# ChassisPowerDistribution_B_1_0_RW.net
KiCad netlist of a schematic drawn in Altium Designer
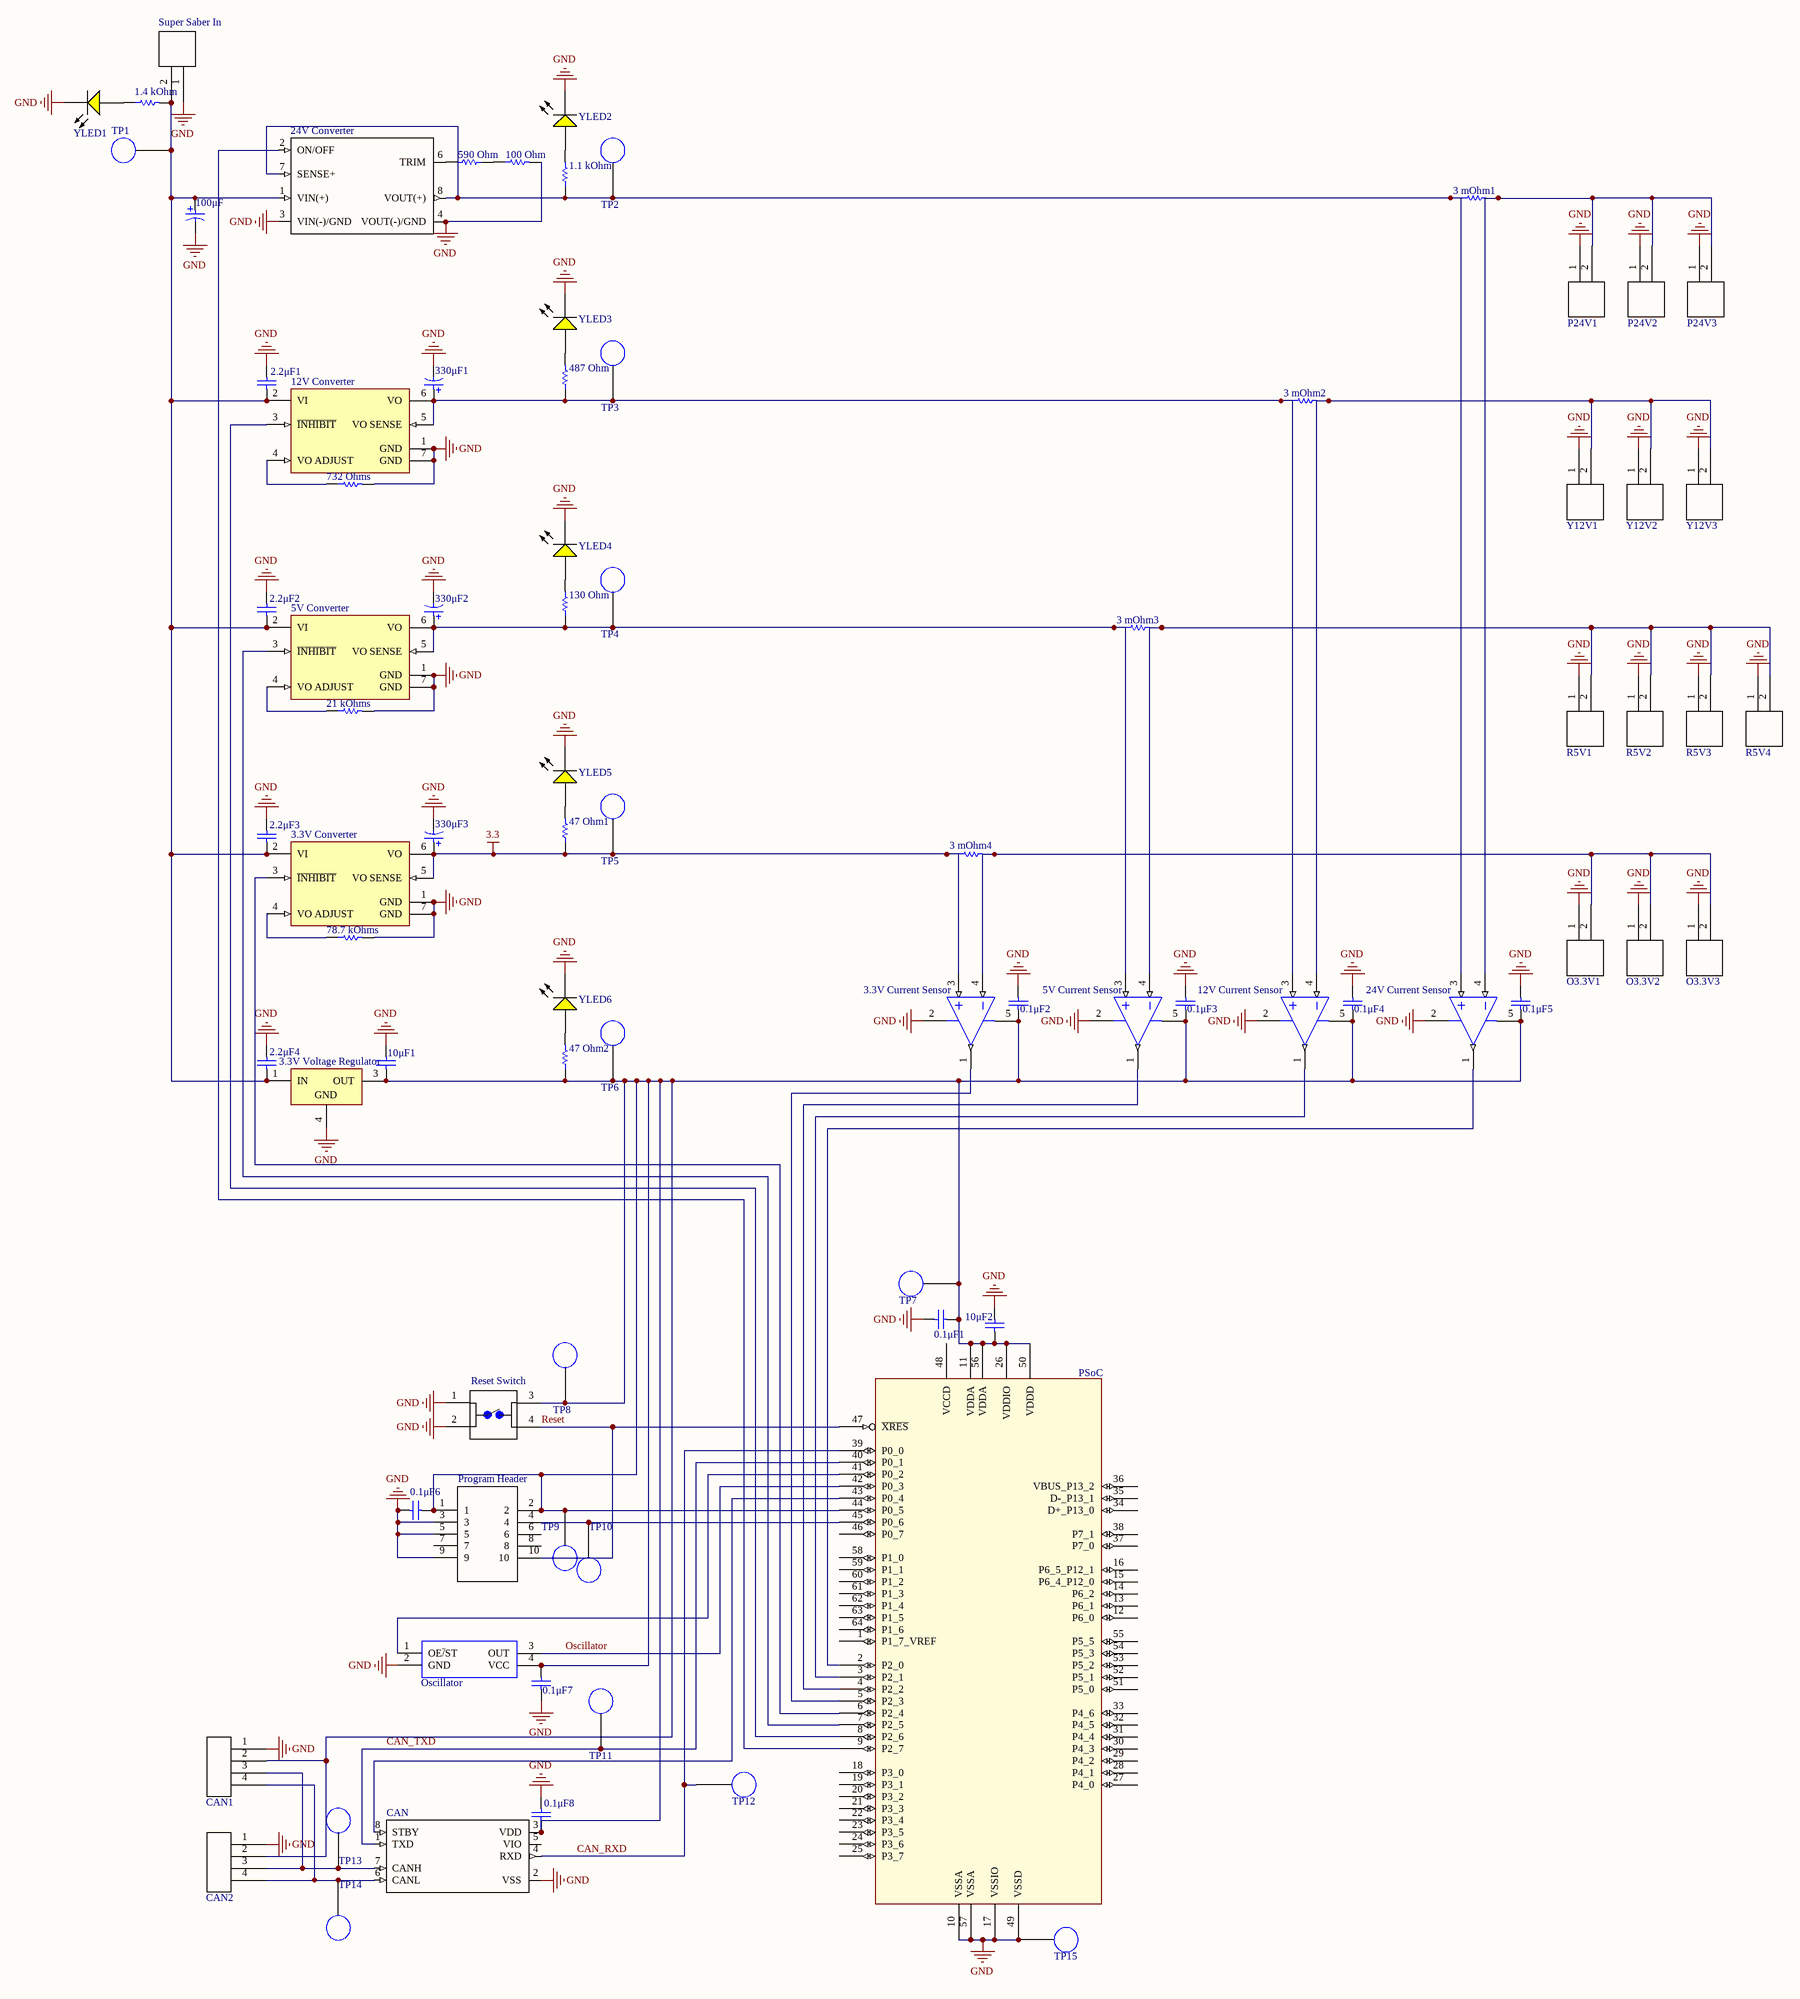
[diagram p0: ChassisPowerDistribution_B_1.0_RW.SchDoc]

(export (version "E")
  (design (tool "Eeschema 10.0.6"))
  (components
    (comp (ref "0.1μF1")
      (value "C0805C104Z5VACTU")
      (footprint "CAPC2013X145X50LL20T25")
      (fields (field (name "MANUFACTURER") "Kemet"))
      (libsource (lib "Altium Content Vault") (part "CAP"))
    )
    (comp (ref "0.1μF2")
      (value "C0805C104Z5VACTU")
      (footprint "CAPC2013X145X50LL20T25")
      (fields (field (name "MANUFACTURER") "Kemet"))
      (libsource (lib "Altium Content Vault") (part "CAP"))
    )
    (comp (ref "0.1μF3")
      (value "C0805C104Z5VACTU")
      (footprint "CAPC2013X145X50LL20T25")
      (fields (field (name "MANUFACTURER") "Kemet"))
      (libsource (lib "Altium Content Vault") (part "CAP"))
    )
    (comp (ref "0.1μF4")
      (value "C0805C104Z5VACTU")
      (footprint "CAPC2013X145X50LL20T25")
      (fields (field (name "MANUFACTURER") "Kemet"))
      (libsource (lib "Altium Content Vault") (part "CAP"))
    )
    (comp (ref "0.1μF5")
      (value "C0805C104Z5VACTU")
      (footprint "CAPC2013X145X50LL20T25")
      (fields (field (name "MANUFACTURER") "Kemet"))
      (libsource (lib "Altium Content Vault") (part "CAP"))
    )
    (comp (ref "0.1μF6")
      (value "C0805C104Z5VACTU")
      (footprint "CAPC2013X145X50LL20T25")
      (fields (field (name "MANUFACTURER") "Kemet"))
      (libsource (lib "Altium Content Vault") (part "CAP"))
    )
    (comp (ref "0.1μF7")
      (value "C0805C104Z5VACTU")
      (footprint "CAPC2013X145X50LL20T25")
      (fields (field (name "MANUFACTURER") "Kemet"))
      (libsource (lib "Altium Content Vault") (part "CAP"))
    )
    (comp (ref "0.1μF8")
      (value "C0805C104Z5VACTU")
      (footprint "CAPC2013X145X50LL20T25")
      (fields (field (name "MANUFACTURER") "Kemet"))
      (libsource (lib "Altium Content Vault") (part "CAP"))
    )
    (comp (ref "1.1 kOhm")
      (value "ERJ-6GEYJ112V")
      (footprint "RESC2013X70X40ML20T20")
      (fields (field (name "MANUFACTURER") "Panasonic"))
      (libsource (lib "Altium Content Vault") (part "RES"))
    )
    (comp (ref "1.4 kOhm")
      (value "RC0805FR-071K4L")
      (footprint "RESC2013X60X35ML10T20")
      (fields (field (name "MANUFACTURER") "Yageo"))
      (libsource (lib "Altium Content Vault") (part "RES"))
    )
    (comp (ref "2.2μF1")
      (value "C2012X7R1H225K125AC")
      (footprint "CAPC2013X145X20LL20")
      (description "Chip Capacitor, 2.2 uF, +/- 10%, 50 V, -55 to 125 degC, 0805 (2012 Metric), RoHS, Tape and Reel")
      (fields (field (name "MANUFACTURER") "TDK") (field (name "TOLERANCE") "±10%"))
      (libsource (lib "Altium Content Vault") (part "CAP-NP-2"))
    )
    (comp (ref "2.2μF2")
      (value "C2012X7R1H225K125AC")
      (footprint "CAPC2013X145X20LL20")
      (description "Chip Capacitor, 2.2 uF, +/- 10%, 50 V, -55 to 125 degC, 0805 (2012 Metric), RoHS, Tape and Reel")
      (fields (field (name "MANUFACTURER") "TDK") (field (name "TOLERANCE") "±10%"))
      (libsource (lib "Altium Content Vault") (part "CAP-NP-2"))
    )
    (comp (ref "2.2μF3")
      (value "C2012X7R1H225K125AC")
      (footprint "CAPC2013X145X20LL20")
      (description "Chip Capacitor, 2.2 uF, +/- 10%, 50 V, -55 to 125 degC, 0805 (2012 Metric), RoHS, Tape and Reel")
      (fields (field (name "MANUFACTURER") "TDK") (field (name "TOLERANCE") "±10%"))
      (libsource (lib "Altium Content Vault") (part "CAP-NP-2"))
    )
    (comp (ref "2.2μF4")
      (value "C2012X7R1H225K125AC")
      (footprint "CAPC2013X145X20LL20")
      (description "Chip Capacitor, 2.2 uF, +/- 10%, 50 V, -55 to 125 degC, 0805 (2012 Metric), RoHS, Tape and Reel")
      (fields (field (name "MANUFACTURER") "TDK") (field (name "TOLERANCE") "±10%"))
      (libsource (lib "Altium Content Vault") (part "CAP-NP-2"))
    )
    (comp (ref "3 mOhm1")
      (value "OAR5R003JLF")
      (footprint "OAR5R003JLF:OAR5R003JLF")
      (description "Resistor")
      (libsource (lib "Miscellaneous Devices") (part "Res1"))
    )
    (comp (ref "3 mOhm2")
      (value "OAR5R003JLF")
      (footprint "OAR5R003JLF:OAR5R003JLF")
      (description "Resistor")
      (libsource (lib "Miscellaneous Devices") (part "Res1"))
    )
    (comp (ref "3 mOhm3")
      (value "OAR5R003JLF")
      (footprint "OAR5R003JLF:OAR5R003JLF")
      (description "Resistor")
      (libsource (lib "Miscellaneous Devices") (part "Res1"))
    )
    (comp (ref "3 mOhm4")
      (value "OAR5R003JLF")
      (footprint "OAR5R003JLF:OAR5R003JLF")
      (description "Resistor")
      (libsource (lib "Miscellaneous Devices") (part "Res1"))
    )
    (comp (ref "3.3V Converter")
      (value "PTN78020WAH")
      (footprint "EUK0007A")
      (fields (field (name "MANUFACTURER") "Texas Instruments"))
      (libsource (lib "Altium Content Vault") (part "TI-PTN780X0WEUX7_HEUX7"))
    )
    (comp (ref "3.3V Current Sensor")
      (value "INA194AIDBVR")
      (footprint "DBV0005A_M")
      (fields (field (name "MANUFACTURER") "Texas Instruments"))
      (libsource (lib "Altium Content Vault") (part "TI-INA1XXDBV5"))
    )
    (comp (ref "3.3V Voltage Regulator")
      (value "LP2950CDTX-3.3")
      (footprint "TD03B_M")
      (description "Series of Adjustable Micropower Voltage Regulators, 3-pin TO-252")
      (fields (field (name "MANUFACTURER") "National Semiconductor"))
      (libsource (lib "Altium Content Vault") (part "PM-REG-LM78M05-SOT3"))
    )
    (comp (ref "5V Converter")
      (value "PTN78020WAH")
      (footprint "EUK0007A")
      (fields (field (name "MANUFACTURER") "Texas Instruments"))
      (libsource (lib "Altium Content Vault") (part "TI-PTN780X0WEUX7_HEUX7"))
    )
    (comp (ref "5V Current Sensor")
      (value "INA194AIDBVR")
      (footprint "DBV0005A_M")
      (fields (field (name "MANUFACTURER") "Texas Instruments"))
      (libsource (lib "Altium Content Vault") (part "TI-INA1XXDBV5"))
    )
    (comp (ref "10μF1")
      (value "TPSR106K006R1000")
      (footprint "CAPC2113X140X50ML20T30")
      (fields (field (name "MANUFACTURER") "AVX Interconnect / Elco"))
      (libsource (lib "Altium Content Vault") (part "CAP"))
    )
    (comp (ref "10μF2")
      (value "TPSR106K006R1000")
      (footprint "CAPC2113X140X50ML20T30")
      (fields (field (name "MANUFACTURER") "AVX Interconnect / Elco"))
      (libsource (lib "Altium Content Vault") (part "CAP"))
    )
    (comp (ref "12V Converter")
      (value "PTN78020WAH")
      (footprint "EUK0007A")
      (fields (field (name "MANUFACTURER") "Texas Instruments"))
      (libsource (lib "Altium Content Vault") (part "TI-PTN780X0WEUX7_HEUX7"))
    )
    (comp (ref "12V Current Sensor")
      (value "INA194AIDBVR")
      (footprint "DBV0005A_M")
      (fields (field (name "MANUFACTURER") "Texas Instruments"))
      (libsource (lib "Altium Content Vault") (part "TI-INA1XXDBV5"))
    )
    (comp (ref "21 kOhms")
      (value "ERJ-6ENF2102V")
      (footprint "RESC2013X70X40ML20T20")
      (fields (field (name "MANUFACTURER") "Panasonic"))
      (libsource (lib "Altium Content Vault") (part "RES"))
    )
    (comp (ref "24V Converter")
      (value "I6A4W010A033V-001-R")
      (footprint "*TDK-LAMBDA_I6A4W020A033V-001-R")
      (description "Dc-Dc, Pcb Mount, Sixteenth Brick, Input 24vdc, Output 3.3-40v 20a, 250w, Neg Logic")
      (fields (field (name "DIGI-KEY_PART_NUMBER") "285-2670-ND") (field (name "MF") "TDK-Lambda Americas"))
      (libsource (lib "*") (part "I6A4W020A033V-001-R"))
    )
    (comp (ref "24V Current Sensor")
      (value "INA194AIDBVR")
      (footprint "DBV0005A_M")
      (fields (field (name "MANUFACTURER") "Texas Instruments"))
      (libsource (lib "Altium Content Vault") (part "TI-INA1XXDBV5"))
    )
    (comp (ref "47 Ohm1")
      (value "RR1220Q-470-D")
      (footprint "RESC2013X50X40LL20T20")
      (fields (field (name "MANUFACTURER") "Susumu"))
      (libsource (lib "Altium Content Vault") (part "RES"))
    )
    (comp (ref "47 Ohm2")
      (value "RR1220Q-470-D")
      (footprint "RESC2013X50X40LL20T20")
      (fields (field (name "MANUFACTURER") "Susumu"))
      (libsource (lib "Altium Content Vault") (part "RES"))
    )
    (comp (ref "78.7 kOhms")
      (value "ERJ-6ENF7872V")
      (footprint "RESC2013X70X40LL20T20")
      (fields (field (name "MANUFACTURER") "Panasonic"))
      (libsource (lib "Altium Content Vault") (part "RES"))
    )
    (comp (ref "100 Ohm")
      (value "ERJ-6ENF1000V")
      (footprint "RESC2013X70X40LL20T20")
      (description "Chip Resistor, 100 Ohm, +/- 1%, 0.125 W, -55 to 155 degC, 0805 (2012 Metric), RoHS, Tape and Reel")
      (fields (field (name "MANUFACTURER") "Panasonic"))
      (libsource (lib "Altium Content Vault") (part "RES-2"))
    )
    (comp (ref "100μF")
      (value "EEU-FC1V101")
      (footprint "CAPPRD350W60D800H2000:*CAPPRD350W60D800H2000")
      (fields (field (name "MANUFACTURER") "Panasonic"))
      (libsource (lib "CAPPRD350W60D800H2000") (part "PNSC-CAP-P-2"))
    )
    (comp (ref "130 Ohm")
      (value "RC0805JR-07130RL")
      (footprint "RESC2013X60X35ML10T20")
      (fields (field (name "MANUFACTURER") "Yageo"))
      (libsource (lib "Altium Content Vault") (part "RES"))
    )
    (comp (ref "330μF1")
      (value "EEU-FC1V331B")
      (footprint "CAPPRD350W60D800H2000:*CAPPRD350W60D800H2000")
      (fields (field (name "MANUFACTURER") "Panasonic"))
      (libsource (lib "CAPPRD350W60D800H2000") (part "PNSC-CAP-P-2"))
    )
    (comp (ref "330μF2")
      (value "EEU-FC1V331B")
      (footprint "CAPPRD350W60D800H2000:*CAPPRD350W60D800H2000")
      (fields (field (name "MANUFACTURER") "Panasonic"))
      (libsource (lib "CAPPRD350W60D800H2000") (part "PNSC-CAP-P-2"))
    )
    (comp (ref "330μF3")
      (value "EEU-FC1V331B")
      (footprint "CAPPRD350W60D800H2000:*CAPPRD350W60D800H2000")
      (fields (field (name "MANUFACTURER") "Panasonic"))
      (libsource (lib "CAPPRD350W60D800H2000") (part "PNSC-CAP-P-2"))
    )
    (comp (ref "487 Ohm")
      (value "RC0805FR-07487RL")
      (footprint "RESC2013X60X35NL10T20")
      (fields (field (name "MANUFACTURER") "Yageo"))
      (libsource (lib "Altium Content Vault") (part "RES"))
    )
    (comp (ref "590 Ohm")
      (value "ERJ-6ENF5900V")
      (footprint "RESC2013X70X40LL20T20")
      (fields (field (name "MANUFACTURER") "Panasonic"))
      (libsource (lib "Altium Content Vault") (part "RES"))
    )
    (comp (ref "732 Ohms")
      (value "ERJ-6ENF7320V")
      (footprint "RESC2013X70X40LL20T20")
      (fields (field (name "MANUFACTURER") "Panasonic"))
      (libsource (lib "Altium Content Vault") (part "RES"))
    )
    (comp (ref "CAN")
      (value "MCP2562-E/SN")
      (footprint "CAN Tranceiver:SOIC127P600X175-8N")
      (description "Microchip MCP2562-E/SN, CAN Transceiver 1MBps 1-channel IEC 61000-4-2, 8-Pin SOIC")
      (fields (field (name "MF") "Microchip"))
      (libsource (lib "*") (part "MCP2562-E/SN"))
    )
    (comp (ref "CAN1")
      (value "Molex Micro")
      (footprint "0430450427")
      (description "Molex micro-fit 3.0 dual row header. P/N 0430450427")
      (libsource (lib "*") (part "Molex micro-fit 4-pin (Single row schematic)"))
    )
    (comp (ref "CAN2")
      (value "Molex Micro")
      (footprint "0430450427")
      (description "Molex micro-fit 3.0 dual row header. P/N 0430450427")
      (libsource (lib "*") (part "Molex micro-fit 4-pin (Single row schematic)"))
    )
    (comp (ref "O3.3V1")
      (value "*")
      (footprint "Connector Footprints:1510482204")
      (libsource (lib "*") (part "Molex 6.5MM  power connector"))
    )
    (comp (ref "O3.3V2")
      (value "*")
      (footprint "Connector Footprints:1510482204")
      (libsource (lib "*") (part "Molex 6.5MM  power connector"))
    )
    (comp (ref "O3.3V3")
      (value "*")
      (footprint "Connector Footprints:1510482204")
      (libsource (lib "*") (part "Molex 6.5MM  power connector"))
    )
    (comp (ref "Oscillator")
      (value "SG-636PCW_50.0000MC3__ROHS")
      (footprint "Oscillator:SG-636")
      (description "Standard Clock Oscillators 50MHz 3.3Volt 100ppm -20C +70C")
      (fields (field (name "MANUFACTURER_PART_NUMBER") "SG-636PCW 50.0000MC3: ROHS"))
      (libsource (lib "*") (part "SG-636"))
    )
    (comp (ref "P24V1")
      (value "*")
      (footprint "Connector Footprints:1510482204")
      (libsource (lib "*") (part "Molex 6.5MM  power connector"))
    )
    (comp (ref "P24V2")
      (value "*")
      (footprint "Connector Footprints:1510482204")
      (libsource (lib "*") (part "Molex 6.5MM  power connector"))
    )
    (comp (ref "P24V3")
      (value "*")
      (footprint "Connector Footprints:1510482204")
      (libsource (lib "*") (part "Molex 6.5MM  power connector"))
    )
    (comp (ref "Program Header")
      (value "*")
      (footprint "Connector Footprints:SAMTEC-FTSH-105-01-X-D")
      (libsource (lib "*") (part "SAMTEC-FTSH-105-01-X-D"))
    )
    (comp (ref "PSoC")
      (value "CY8C4248AZI-L485")
      (footprint "PSOC:TQFP50P1200X1200X160-64N")
      (libsource (lib "*") (part "CY8C4248AZI-L485"))
    )
    (comp (ref "R5V1")
      (value "*")
      (footprint "Connector Footprints:1510482204")
      (libsource (lib "*") (part "Molex 6.5MM  power connector"))
    )
    (comp (ref "R5V2")
      (value "*")
      (footprint "Connector Footprints:1510482204")
      (libsource (lib "*") (part "Molex 6.5MM  power connector"))
    )
    (comp (ref "R5V3")
      (value "*")
      (footprint "Connector Footprints:1510482204")
      (libsource (lib "*") (part "Molex 6.5MM  power connector"))
    )
    (comp (ref "R5V4")
      (value "*")
      (footprint "Connector Footprints:1510482204")
      (libsource (lib "*") (part "Molex 6.5MM  power connector"))
    )
    (comp (ref "Reset Switch")
      (value "1825910-7")
      (footprint "Switch 6mm 24V:Switch 6mm 24V (NO)")
      (description "FSM4JAH=6MM TACT SWITCH, HIGH TEMP")
      (fields (field (name "MF") "TE Connectivity") (field (name "DIGI-KEY_PART_NUMBER") "450-1804-ND"))
      (libsource (lib "*") (part "Switch 6mm 24V (NO)"))
    )
    (comp (ref "Super Saber In") (value "*") (libsource (lib "*") (part "Super Saber")))
    (comp (ref "TP1")
      (value "*")
      (footprint "Test Point Through-hole")
      (libsource (lib "*") (part "Test Point"))
    )
    (comp (ref "TP2")
      (value "*")
      (footprint "Test Point Through-hole")
      (libsource (lib "*") (part "Test Point"))
    )
    (comp (ref "TP3")
      (value "*")
      (footprint "Test Point Through-hole")
      (libsource (lib "*") (part "Test Point"))
    )
    (comp (ref "TP4")
      (value "*")
      (footprint "Test Point Through-hole")
      (libsource (lib "*") (part "Test Point"))
    )
    (comp (ref "TP5")
      (value "*")
      (footprint "Test Point Through-hole")
      (libsource (lib "*") (part "Test Point"))
    )
    (comp (ref "TP6")
      (value "*")
      (footprint "Test Point Through-hole")
      (libsource (lib "*") (part "Test Point"))
    )
    (comp (ref "TP7")
      (value "*")
      (footprint "Test Point Through-hole")
      (libsource (lib "*") (part "Test Point"))
    )
    (comp (ref "TP8")
      (value "*")
      (footprint "Test Point Through-hole")
      (libsource (lib "*") (part "Test Point"))
    )
    (comp (ref "TP9")
      (value "*")
      (footprint "Test Point Through-hole")
      (libsource (lib "*") (part "Test Point"))
    )
    (comp (ref "TP10")
      (value "*")
      (footprint "Test Point Through-hole")
      (libsource (lib "*") (part "Test Point"))
    )
    (comp (ref "TP11")
      (value "*")
      (footprint "Test Point Through-hole")
      (libsource (lib "*") (part "Test Point"))
    )
    (comp (ref "TP12")
      (value "*")
      (footprint "Test Point Through-hole")
      (libsource (lib "*") (part "Test Point"))
    )
    (comp (ref "TP13")
      (value "*")
      (footprint "Test Point Through-hole")
      (libsource (lib "*") (part "Test Point"))
    )
    (comp (ref "TP14")
      (value "*")
      (footprint "Test Point Through-hole")
      (libsource (lib "*") (part "Test Point"))
    )
    (comp (ref "TP15")
      (value "*")
      (footprint "Test Point Through-hole")
      (libsource (lib "*") (part "Test Point"))
    )
    (comp (ref "Y12V1")
      (value "*")
      (footprint "Connector Footprints:1510482204")
      (libsource (lib "*") (part "Molex 6.5MM  power connector"))
    )
    (comp (ref "Y12V2")
      (value "*")
      (footprint "Connector Footprints:1510482204")
      (libsource (lib "*") (part "Molex 6.5MM  power connector"))
    )
    (comp (ref "Y12V3")
      (value "*")
      (footprint "1510482204")
      (libsource (lib "*") (part "Molex 6.5MM  power connector"))
    )
    (comp (ref "YLED1")
      (value "LTST-C170KSKT")
      (footprint "LTST-C170KSKT_V")
      (description "LED Yellow, 75 mW, 80 mA, -55 to 85 degC, 2-Pin SMD, RoHS, Tape and Reel")
      (fields (field (name "MANUFACTURER") "Lite-On"))
      (libsource (lib "Altium Content Vault") (part "LED-YELLOW-AK-2"))
    )
    (comp (ref "YLED2")
      (value "LTST-C170KSKT")
      (footprint "LTST-C170KSKT_V")
      (description "LED Yellow, 75 mW, 80 mA, -55 to 85 degC, 2-Pin SMD, RoHS, Tape and Reel")
      (fields (field (name "MANUFACTURER") "Lite-On"))
      (libsource (lib "Altium Content Vault") (part "LED-YELLOW-AK-2"))
    )
    (comp (ref "YLED3")
      (value "LTST-C170KSKT")
      (footprint "LTST-C170KSKT_V")
      (description "LED Yellow, 75 mW, 80 mA, -55 to 85 degC, 2-Pin SMD, RoHS, Tape and Reel")
      (fields (field (name "MANUFACTURER") "Lite-On"))
      (libsource (lib "Altium Content Vault") (part "LED-YELLOW-AK-2"))
    )
    (comp (ref "YLED4")
      (value "LTST-C170KSKT")
      (footprint "LTST-C170KSKT_V")
      (description "LED Yellow, 75 mW, 80 mA, -55 to 85 degC, 2-Pin SMD, RoHS, Tape and Reel")
      (fields (field (name "MANUFACTURER") "Lite-On"))
      (libsource (lib "Altium Content Vault") (part "LED-YELLOW-AK-2"))
    )
    (comp (ref "YLED5")
      (value "LTST-C170KSKT")
      (footprint "LTST-C170KSKT_V")
      (description "LED Yellow, 75 mW, 80 mA, -55 to 85 degC, 2-Pin SMD, RoHS, Tape and Reel")
      (fields (field (name "MANUFACTURER") "Lite-On"))
      (libsource (lib "Altium Content Vault") (part "LED-YELLOW-AK-2"))
    )
    (comp (ref "YLED6")
      (value "LTST-C170KSKT")
      (footprint "LTST-C170KSKT_V")
      (description "LED Yellow, 75 mW, 80 mA, -55 to 85 degC, 2-Pin SMD, RoHS, Tape and Reel")
      (fields (field (name "MANUFACTURER") "Lite-On"))
      (libsource (lib "Altium Content Vault") (part "LED-YELLOW-AK-2"))
    )
  )
  (nets
    (net (code "1") (name "/CAN_RXD") (class "Default")
      (node (ref "CAN") (pin "4") (pinfunction "RXD_4") (pintype "output"))
      (node (ref "PSoC") (pin "39") (pinfunction "P0_0_39") (pintype "bidirectional"))
      (node (ref "TP12") (pin "1") (pinfunction "1_1") (pintype "passive"))
    )
    (net (code "2") (name "/CAN_TXD") (class "Default")
      (node (ref "CAN") (pin "1") (pinfunction "TXD_1") (pintype "input"))
      (node (ref "PSoC") (pin "40") (pinfunction "P0_1_40") (pintype "bidirectional"))
      (node (ref "TP11") (pin "1") (pinfunction "1_1") (pintype "passive"))
    )
    (net (code "3") (name "/Oscillator") (class "Default")
      (node (ref "Oscillator") (pin "3") (pinfunction "OUT_3") (pintype "passive"))
      (node (ref "PSoC") (pin "42") (pinfunction "P0_3_42") (pintype "bidirectional"))
    )
    (net (code "4") (name "/Reset") (class "Default")
      (node (ref "PSoC") (pin "47") (pinfunction "~{XRES}_47") (pintype "input"))
      (node (ref "Program Header") (pin "10") (pinfunction "10_10") (pintype "passive"))
      (node (ref "Reset Switch") (pin "4") (pinfunction "4_4") (pintype "passive"))
    )
    (net (code "5") (name "3.3") (class "Default")
      (node (ref "3 mOhm4") (pin "1") (pinfunction "1_1") (pintype "passive"))
      (node (ref "3.3V Converter") (pin "5") (pinfunction "VO_SENSE_5") (pintype "input"))
      (node (ref "3.3V Converter") (pin "6") (pinfunction "VO_6") (pintype "power_in"))
      (node (ref "3.3V Current Sensor") (pin "3") (pinfunction "VIN+_3") (pintype "input"))
      (node (ref "330μF3") (pin "1") (pinfunction "1_1") (pintype "passive"))
      (node (ref "47 Ohm1") (pin "1") (pinfunction "1_1") (pintype "passive"))
      (node (ref "TP5") (pin "1") (pinfunction "1_1") (pintype "passive"))
    )
    (net (code "6") (name "GND") (class "Default")
      (node (ref "0.1μF1") (pin "1") (pinfunction "1_1") (pintype "passive"))
      (node (ref "0.1μF2") (pin "2") (pinfunction "2_2") (pintype "passive"))
      (node (ref "0.1μF3") (pin "2") (pinfunction "2_2") (pintype "passive"))
      (node (ref "0.1μF4") (pin "2") (pinfunction "2_2") (pintype "passive"))
      (node (ref "0.1μF5") (pin "2") (pinfunction "2_2") (pintype "passive"))
      (node (ref "0.1μF6") (pin "1") (pinfunction "1_1") (pintype "passive"))
      (node (ref "0.1μF7") (pin "2") (pinfunction "2_2") (pintype "passive"))
      (node (ref "0.1μF8") (pin "2") (pinfunction "2_2") (pintype "passive"))
      (node (ref "100 Ohm") (pin "2") (pinfunction "2_2") (pintype "passive"))
      (node (ref "100μF") (pin "2") (pinfunction "2_2") (pintype "passive"))
      (node (ref "10μF1") (pin "2") (pinfunction "2_2") (pintype "passive"))
      (node (ref "10μF2") (pin "2") (pinfunction "2_2") (pintype "passive"))
      (node (ref "12V Converter") (pin "1") (pinfunction "GND_1") (pintype "power_in"))
      (node (ref "12V Converter") (pin "7") (pinfunction "GND_7") (pintype "power_in"))
      (node (ref "12V Current Sensor") (pin "2") (pinfunction "GND_2") (pintype "power_in"))
      (node (ref "2.2μF1") (pin "2") (pinfunction "2_2") (pintype "passive"))
      (node (ref "2.2μF2") (pin "2") (pinfunction "2_2") (pintype "passive"))
      (node (ref "2.2μF3") (pin "2") (pinfunction "2_2") (pintype "passive"))
      (node (ref "2.2μF4") (pin "2") (pinfunction "2_2") (pintype "passive"))
      (node (ref "21 kOhms") (pin "2") (pinfunction "2_2") (pintype "passive"))
      (node (ref "24V Converter") (pin "3") (pinfunction "VIN(-)/GND_3") (pintype "power_in"))
      (node (ref "24V Converter") (pin "4") (pinfunction "VOUT(-)/GND_4") (pintype "power_in"))
      (node (ref "24V Current Sensor") (pin "2") (pinfunction "GND_2") (pintype "power_in"))
      (node (ref "3.3V Converter") (pin "1") (pinfunction "GND_1") (pintype "power_in"))
      (node (ref "3.3V Converter") (pin "7") (pinfunction "GND_7") (pintype "power_in"))
      (node (ref "3.3V Current Sensor") (pin "2") (pinfunction "GND_2") (pintype "power_in"))
      (node (ref "3.3V Voltage Regulator") (pin "4") (pinfunction "GND_4") (pintype "power_in"))
      (node (ref "330μF1") (pin "2") (pinfunction "2_2") (pintype "passive"))
      (node (ref "330μF2") (pin "2") (pinfunction "2_2") (pintype "passive"))
      (node (ref "330μF3") (pin "2") (pinfunction "2_2") (pintype "passive"))
      (node (ref "5V Converter") (pin "1") (pinfunction "GND_1") (pintype "power_in"))
      (node (ref "5V Converter") (pin "7") (pinfunction "GND_7") (pintype "power_in"))
      (node (ref "5V Current Sensor") (pin "2") (pinfunction "GND_2") (pintype "power_in"))
      (node (ref "732 Ohms") (pin "2") (pinfunction "2_2") (pintype "passive"))
      (node (ref "78.7 kOhms") (pin "2") (pinfunction "2_2") (pintype "passive"))
      (node (ref "CAN") (pin "2") (pinfunction "VSS_2") (pintype "power_in"))
      (node (ref "CAN1") (pin "1") (pintype "passive"))
      (node (ref "CAN2") (pin "1") (pintype "passive"))
      (node (ref "O3.3V1") (pin "1") (pintype "passive"))
      (node (ref "O3.3V2") (pin "1") (pintype "passive"))
      (node (ref "O3.3V3") (pin "1") (pintype "passive"))
      (node (ref "Oscillator") (pin "2") (pinfunction "GND_2") (pintype "passive"))
      (node (ref "P24V1") (pin "1") (pintype "passive"))
      (node (ref "P24V2") (pin "1") (pintype "passive"))
      (node (ref "P24V3") (pin "1") (pintype "passive"))
      (node (ref "PSoC") (pin "10") (pinfunction "VSSA_10") (pintype "power_in"))
      (node (ref "PSoC") (pin "17") (pinfunction "VSSIO_17") (pintype "power_in"))
      (node (ref "PSoC") (pin "49") (pinfunction "VSSD_49") (pintype "power_in"))
      (node (ref "PSoC") (pin "57") (pinfunction "VSSA_57") (pintype "power_in"))
      (node (ref "Program Header") (pin "3") (pinfunction "3_3") (pintype "passive"))
      (node (ref "Program Header") (pin "5") (pinfunction "5_5") (pintype "passive"))
      (node (ref "Program Header") (pin "9") (pinfunction "9_9") (pintype "passive"))
      (node (ref "R5V1") (pin "1") (pintype "passive"))
      (node (ref "R5V2") (pin "1") (pintype "passive"))
      (node (ref "R5V3") (pin "1") (pintype "passive"))
      (node (ref "R5V4") (pin "1") (pintype "passive"))
      (node (ref "Reset Switch") (pin "1") (pinfunction "1_1") (pintype "passive"))
      (node (ref "Reset Switch") (pin "2") (pinfunction "2_2") (pintype "passive"))
      (node (ref "Super Saber In") (pin "1") (pintype "passive"))
      (node (ref "TP15") (pin "1") (pinfunction "1_1") (pintype "passive"))
      (node (ref "Y12V1") (pin "1") (pintype "passive"))
      (node (ref "Y12V2") (pin "1") (pintype "passive"))
      (node (ref "Y12V3") (pin "1") (pintype "passive"))
      (node (ref "YLED1") (pin "2") (pinfunction "K_2") (pintype "passive"))
      (node (ref "YLED2") (pin "2") (pinfunction "K_2") (pintype "passive"))
      (node (ref "YLED3") (pin "2") (pinfunction "K_2") (pintype "passive"))
      (node (ref "YLED4") (pin "2") (pinfunction "K_2") (pintype "passive"))
      (node (ref "YLED5") (pin "2") (pinfunction "K_2") (pintype "passive"))
      (node (ref "YLED6") (pin "2") (pinfunction "K_2") (pintype "passive"))
    )
    (net (code "7") (name "Net-(3.3V Converter-VO_ADJUST)") (class "Default")
      (node (ref "3.3V Converter") (pin "4") (pinfunction "VO_ADJUST_4") (pintype "input"))
      (node (ref "78.7 kOhms") (pin "1") (pinfunction "1_1") (pintype "passive"))
    )
    (net (code "8") (name "Net-(3.3V Converter-~{INHIBIT})") (class "Default")
      (node (ref "3.3V Converter") (pin "3") (pinfunction "~{INHIBIT}_3") (pintype "input"))
      (node (ref "PSoC") (pin "6") (pinfunction "P2_4_6") (pintype "bidirectional"))
    )
    (net (code "9") (name "Net-(3.3V Current Sensor-OUT)") (class "Default")
      (node (ref "3.3V Current Sensor") (pin "1") (pinfunction "OUT_1") (pintype "output"))
      (node (ref "PSoC") (pin "5") (pinfunction "P2_3_5") (pintype "bidirectional"))
    )
    (net (code "10") (name "Net-(3.3V Current Sensor-VIN-)") (class "Default")
      (node (ref "3 mOhm4") (pin "2") (pinfunction "2_2") (pintype "passive"))
      (node (ref "3.3V Current Sensor") (pin "4") (pinfunction "VIN-_4") (pintype "input"))
      (node (ref "O3.3V1") (pin "2") (pintype "passive"))
      (node (ref "O3.3V2") (pin "2") (pintype "passive"))
      (node (ref "O3.3V3") (pin "2") (pintype "passive"))
    )
    (net (code "11") (name "Net-(5V Converter-VO)") (class "Default")
      (node (ref "130 Ohm") (pin "1") (pinfunction "1_1") (pintype "passive"))
      (node (ref "3 mOhm3") (pin "1") (pinfunction "1_1") (pintype "passive"))
      (node (ref "330μF2") (pin "1") (pinfunction "1_1") (pintype "passive"))
      (node (ref "5V Converter") (pin "5") (pinfunction "VO_SENSE_5") (pintype "input"))
      (node (ref "5V Converter") (pin "6") (pinfunction "VO_6") (pintype "power_in"))
      (node (ref "5V Current Sensor") (pin "3") (pinfunction "VIN+_3") (pintype "input"))
      (node (ref "TP4") (pin "1") (pinfunction "1_1") (pintype "passive"))
    )
    (net (code "12") (name "Net-(5V Converter-VO_ADJUST)") (class "Default")
      (node (ref "21 kOhms") (pin "1") (pinfunction "1_1") (pintype "passive"))
      (node (ref "5V Converter") (pin "4") (pinfunction "VO_ADJUST_4") (pintype "input"))
    )
    (net (code "13") (name "Net-(5V Converter-~{INHIBIT})") (class "Default")
      (node (ref "5V Converter") (pin "3") (pinfunction "~{INHIBIT}_3") (pintype "input"))
      (node (ref "PSoC") (pin "7") (pinfunction "P2_5_7") (pintype "bidirectional"))
    )
    (net (code "14") (name "Net-(5V Current Sensor-OUT)") (class "Default")
      (node (ref "5V Current Sensor") (pin "1") (pinfunction "OUT_1") (pintype "output"))
      (node (ref "PSoC") (pin "4") (pinfunction "P2_2_4") (pintype "bidirectional"))
    )
    (net (code "15") (name "Net-(5V Current Sensor-VIN-)") (class "Default")
      (node (ref "3 mOhm3") (pin "2") (pinfunction "2_2") (pintype "passive"))
      (node (ref "5V Current Sensor") (pin "4") (pinfunction "VIN-_4") (pintype "input"))
      (node (ref "R5V1") (pin "2") (pintype "passive"))
      (node (ref "R5V2") (pin "2") (pintype "passive"))
      (node (ref "R5V3") (pin "2") (pintype "passive"))
      (node (ref "R5V4") (pin "2") (pintype "passive"))
    )
    (net (code "16") (name "Net-(12V Converter-VI)") (class "Default")
      (node (ref "1.4 kOhm") (pin "2") (pinfunction "2_2") (pintype "passive"))
      (node (ref "100μF") (pin "1") (pinfunction "1_1") (pintype "passive"))
      (node (ref "12V Converter") (pin "2") (pinfunction "VI_2") (pintype "power_in"))
      (node (ref "2.2μF1") (pin "1") (pinfunction "1_1") (pintype "passive"))
      (node (ref "2.2μF2") (pin "1") (pinfunction "1_1") (pintype "passive"))
      (node (ref "2.2μF3") (pin "1") (pinfunction "1_1") (pintype "passive"))
      (node (ref "2.2μF4") (pin "1") (pinfunction "1_1") (pintype "passive"))
      (node (ref "24V Converter") (pin "1") (pinfunction "VIN(+)_1") (pintype "input"))
      (node (ref "3.3V Converter") (pin "2") (pinfunction "VI_2") (pintype "power_in"))
      (node (ref "3.3V Voltage Regulator") (pin "1") (pinfunction "IN_1") (pintype "power_in"))
      (node (ref "5V Converter") (pin "2") (pinfunction "VI_2") (pintype "power_in"))
      (node (ref "Super Saber In") (pin "2") (pintype "passive"))
      (node (ref "TP1") (pin "1") (pinfunction "1_1") (pintype "passive"))
    )
    (net (code "17") (name "Net-(12V Converter-VO)") (class "Default")
      (node (ref "12V Converter") (pin "5") (pinfunction "VO_SENSE_5") (pintype "input"))
      (node (ref "12V Converter") (pin "6") (pinfunction "VO_6") (pintype "power_in"))
      (node (ref "12V Current Sensor") (pin "3") (pinfunction "VIN+_3") (pintype "input"))
      (node (ref "3 mOhm2") (pin "1") (pinfunction "1_1") (pintype "passive"))
      (node (ref "330μF1") (pin "1") (pinfunction "1_1") (pintype "passive"))
      (node (ref "487 Ohm") (pin "1") (pinfunction "1_1") (pintype "passive"))
      (node (ref "TP3") (pin "1") (pinfunction "1_1") (pintype "passive"))
    )
    (net (code "18") (name "Net-(12V Converter-VO_ADJUST)") (class "Default")
      (node (ref "12V Converter") (pin "4") (pinfunction "VO_ADJUST_4") (pintype "input"))
      (node (ref "732 Ohms") (pin "1") (pinfunction "1_1") (pintype "passive"))
    )
    (net (code "19") (name "Net-(12V Converter-~{INHIBIT})") (class "Default")
      (node (ref "12V Converter") (pin "3") (pinfunction "~{INHIBIT}_3") (pintype "input"))
      (node (ref "PSoC") (pin "8") (pinfunction "P2_6_8") (pintype "bidirectional"))
    )
    (net (code "20") (name "Net-(12V Current Sensor-OUT)") (class "Default")
      (node (ref "12V Current Sensor") (pin "1") (pinfunction "OUT_1") (pintype "output"))
      (node (ref "PSoC") (pin "3") (pinfunction "P2_1_3") (pintype "bidirectional"))
    )
    (net (code "21") (name "Net-(12V Current Sensor-V+)") (class "Default")
      (node (ref "0.1μF1") (pin "2") (pinfunction "2_2") (pintype "passive"))
      (node (ref "0.1μF2") (pin "1") (pinfunction "1_1") (pintype "passive"))
      (node (ref "0.1μF3") (pin "1") (pinfunction "1_1") (pintype "passive"))
      (node (ref "0.1μF4") (pin "1") (pinfunction "1_1") (pintype "passive"))
      (node (ref "0.1μF5") (pin "1") (pinfunction "1_1") (pintype "passive"))
      (node (ref "0.1μF6") (pin "2") (pinfunction "2_2") (pintype "passive"))
      (node (ref "0.1μF7") (pin "1") (pinfunction "1_1") (pintype "passive"))
      (node (ref "0.1μF8") (pin "1") (pinfunction "1_1") (pintype "passive"))
      (node (ref "10μF1") (pin "1") (pinfunction "1_1") (pintype "passive"))
      (node (ref "10μF2") (pin "1") (pinfunction "1_1") (pintype "passive"))
      (node (ref "12V Current Sensor") (pin "5") (pinfunction "V+_5") (pintype "power_in"))
      (node (ref "24V Current Sensor") (pin "5") (pinfunction "V+_5") (pintype "power_in"))
      (node (ref "3.3V Current Sensor") (pin "5") (pinfunction "V+_5") (pintype "power_in"))
      (node (ref "3.3V Voltage Regulator") (pin "3") (pinfunction "OUT_3") (pintype "power_in"))
      (node (ref "47 Ohm2") (pin "1") (pinfunction "1_1") (pintype "passive"))
      (node (ref "5V Current Sensor") (pin "5") (pinfunction "V+_5") (pintype "power_in"))
      (node (ref "CAN") (pin "3") (pinfunction "VDD_3") (pintype "power_in"))
      (node (ref "CAN1") (pin "2") (pintype "passive"))
      (node (ref "CAN2") (pin "2") (pintype "passive"))
      (node (ref "Oscillator") (pin "4") (pinfunction "VCC_4") (pintype "power_in"))
      (node (ref "PSoC") (pin "11") (pinfunction "VDDA_11") (pintype "power_in"))
      (node (ref "PSoC") (pin "26") (pinfunction "VDDIO_26") (pintype "power_in"))
      (node (ref "PSoC") (pin "44") (pinfunction "P0_5_44") (pintype "bidirectional"))
      (node (ref "PSoC") (pin "50") (pinfunction "VDDD_50") (pintype "power_in"))
      (node (ref "PSoC") (pin "56") (pinfunction "VDDA_56") (pintype "power_in"))
      (node (ref "Program Header") (pin "1") (pinfunction "1_1") (pintype "passive"))
      (node (ref "Program Header") (pin "2") (pinfunction "2_2") (pintype "passive"))
      (node (ref "Reset Switch") (pin "3") (pinfunction "3_3") (pintype "passive"))
      (node (ref "TP6") (pin "1") (pinfunction "1_1") (pintype "passive"))
      (node (ref "TP7") (pin "1") (pinfunction "1_1") (pintype "passive"))
      (node (ref "TP8") (pin "1") (pinfunction "1_1") (pintype "passive"))
      (node (ref "TP9") (pin "1") (pinfunction "1_1") (pintype "passive"))
    )
    (net (code "22") (name "Net-(12V Current Sensor-VIN-)") (class "Default")
      (node (ref "12V Current Sensor") (pin "4") (pinfunction "VIN-_4") (pintype "input"))
      (node (ref "3 mOhm2") (pin "2") (pinfunction "2_2") (pintype "passive"))
      (node (ref "Y12V1") (pin "2") (pintype "passive"))
      (node (ref "Y12V2") (pin "2") (pintype "passive"))
      (node (ref "Y12V3") (pin "2") (pintype "passive"))
    )
    (net (code "23") (name "Net-(24V Converter-ON{slash}OFF)") (class "Default")
      (node (ref "24V Converter") (pin "2") (pinfunction "ON/OFF_2") (pintype "input"))
      (node (ref "PSoC") (pin "9") (pinfunction "P2_7_9") (pintype "bidirectional"))
    )
    (net (code "24") (name "Net-(24V Converter-SENSE+)") (class "Default")
      (node (ref "1.1 kOhm") (pin "1") (pinfunction "1_1") (pintype "passive"))
      (node (ref "24V Converter") (pin "7") (pinfunction "SENSE+_7") (pintype "input"))
      (node (ref "24V Converter") (pin "8") (pinfunction "VOUT(+)_8") (pintype "output"))
      (node (ref "24V Current Sensor") (pin "3") (pinfunction "VIN+_3") (pintype "input"))
      (node (ref "3 mOhm1") (pin "1") (pinfunction "1_1") (pintype "passive"))
      (node (ref "TP2") (pin "1") (pinfunction "1_1") (pintype "passive"))
    )
    (net (code "25") (name "Net-(24V Converter-TRIM)") (class "Default")
      (node (ref "24V Converter") (pin "6") (pinfunction "TRIM_6") (pintype "passive"))
      (node (ref "590 Ohm") (pin "2") (pinfunction "2_2") (pintype "passive"))
    )
    (net (code "26") (name "Net-(24V Current Sensor-OUT)") (class "Default")
      (node (ref "24V Current Sensor") (pin "1") (pinfunction "OUT_1") (pintype "output"))
      (node (ref "PSoC") (pin "2") (pinfunction "P2_0_2") (pintype "bidirectional"))
    )
    (net (code "27") (name "Net-(24V Current Sensor-VIN-)") (class "Default")
      (node (ref "24V Current Sensor") (pin "4") (pinfunction "VIN-_4") (pintype "input"))
      (node (ref "3 mOhm1") (pin "2") (pinfunction "2_2") (pintype "passive"))
      (node (ref "P24V1") (pin "2") (pintype "passive"))
      (node (ref "P24V2") (pin "2") (pintype "passive"))
      (node (ref "P24V3") (pin "2") (pintype "passive"))
    )
    (net (code "28") (name "Net-(100 Ohm-Pad1)") (class "Default")
      (node (ref "100 Ohm") (pin "1") (pinfunction "1_1") (pintype "passive"))
      (node (ref "590 Ohm") (pin "1") (pinfunction "1_1") (pintype "passive"))
    )
    (net (code "29") (name "Net-(CAN-CANH)") (class "Default")
      (node (ref "CAN") (pin "7") (pinfunction "CANH_7") (pintype "input"))
      (node (ref "CAN1") (pin "3") (pintype "passive"))
      (node (ref "CAN2") (pin "3") (pintype "passive"))
      (node (ref "TP13") (pin "1") (pinfunction "1_1") (pintype "passive"))
    )
    (net (code "30") (name "Net-(CAN-CANL)") (class "Default")
      (node (ref "CAN") (pin "6") (pinfunction "CANL_6") (pintype "input"))
      (node (ref "CAN1") (pin "4") (pintype "passive"))
      (node (ref "CAN2") (pin "4") (pintype "passive"))
      (node (ref "TP14") (pin "1") (pinfunction "1_1") (pintype "passive"))
    )
    (net (code "31") (name "Net-(CAN-STBY)") (class "Default")
      (node (ref "CAN") (pin "8") (pinfunction "STBY_8") (pintype "input"))
      (node (ref "PSoC") (pin "43") (pinfunction "P0_4_43") (pintype "bidirectional"))
    )
    (net (code "32") (name "Net-(Oscillator-OE~{{slash}}ST)") (class "Default")
      (node (ref "Oscillator") (pin "1") (pinfunction "OE~{/}ST_1") (pintype "passive"))
      (node (ref "PSoC") (pin "41") (pinfunction "P0_2_41") (pintype "bidirectional"))
    )
    (net (code "33") (name "Net-(PSoC-P0_6)") (class "Default")
      (node (ref "PSoC") (pin "45") (pinfunction "P0_6_45") (pintype "bidirectional"))
      (node (ref "Program Header") (pin "4") (pinfunction "4_4") (pintype "passive"))
      (node (ref "TP10") (pin "1") (pinfunction "1_1") (pintype "passive"))
    )
    (net (code "34") (name "Net-(YLED1-A)") (class "Default")
      (node (ref "1.4 kOhm") (pin "1") (pinfunction "1_1") (pintype "passive"))
      (node (ref "YLED1") (pin "1") (pinfunction "A_1") (pintype "passive"))
    )
    (net (code "35") (name "Net-(YLED2-A)") (class "Default")
      (node (ref "1.1 kOhm") (pin "2") (pinfunction "2_2") (pintype "passive"))
      (node (ref "YLED2") (pin "1") (pinfunction "A_1") (pintype "passive"))
    )
    (net (code "36") (name "Net-(YLED3-A)") (class "Default")
      (node (ref "487 Ohm") (pin "2") (pinfunction "2_2") (pintype "passive"))
      (node (ref "YLED3") (pin "1") (pinfunction "A_1") (pintype "passive"))
    )
    (net (code "37") (name "Net-(YLED4-A)") (class "Default")
      (node (ref "130 Ohm") (pin "2") (pinfunction "2_2") (pintype "passive"))
      (node (ref "YLED4") (pin "1") (pinfunction "A_1") (pintype "passive"))
    )
    (net (code "38") (name "Net-(YLED5-A)") (class "Default")
      (node (ref "47 Ohm1") (pin "2") (pinfunction "2_2") (pintype "passive"))
      (node (ref "YLED5") (pin "1") (pinfunction "A_1") (pintype "passive"))
    )
    (net (code "39") (name "Net-(YLED6-A)") (class "Default")
      (node (ref "47 Ohm2") (pin "2") (pinfunction "2_2") (pintype "passive"))
      (node (ref "YLED6") (pin "1") (pinfunction "A_1") (pintype "passive"))
    )
    (net (code "40") (name "unconnected-(CAN-VIO-Pad5)") (class "Default")
      (node (ref "CAN") (pin "5") (pinfunction "VIO_5") (pintype "power_in"))
    )
    (net (code "41") (name "unconnected-(PSoC-D+_P13_0-Pad34)") (class "Default")
      (node (ref "PSoC") (pin "34") (pinfunction "D+_P13_0_34") (pintype "bidirectional"))
    )
    (net (code "42") (name "unconnected-(PSoC-D-_P13_1-Pad35)") (class "Default")
      (node (ref "PSoC") (pin "35") (pinfunction "D-_P13_1_35") (pintype "bidirectional"))
    )
    (net (code "43") (name "unconnected-(PSoC-P0_7-Pad46)") (class "Default")
      (node (ref "PSoC") (pin "46") (pinfunction "P0_7_46") (pintype "bidirectional"))
    )
    (net (code "44") (name "unconnected-(PSoC-P1_0-Pad58)") (class "Default")
      (node (ref "PSoC") (pin "58") (pinfunction "P1_0_58") (pintype "bidirectional"))
    )
    (net (code "45") (name "unconnected-(PSoC-P1_1-Pad59)") (class "Default")
      (node (ref "PSoC") (pin "59") (pinfunction "P1_1_59") (pintype "bidirectional"))
    )
    (net (code "46") (name "unconnected-(PSoC-P1_2-Pad60)") (class "Default")
      (node (ref "PSoC") (pin "60") (pinfunction "P1_2_60") (pintype "bidirectional"))
    )
    (net (code "47") (name "unconnected-(PSoC-P1_3-Pad61)") (class "Default")
      (node (ref "PSoC") (pin "61") (pinfunction "P1_3_61") (pintype "bidirectional"))
    )
    (net (code "48") (name "unconnected-(PSoC-P1_4-Pad62)") (class "Default")
      (node (ref "PSoC") (pin "62") (pinfunction "P1_4_62") (pintype "bidirectional"))
    )
    (net (code "49") (name "unconnected-(PSoC-P1_5-Pad63)") (class "Default")
      (node (ref "PSoC") (pin "63") (pinfunction "P1_5_63") (pintype "bidirectional"))
    )
    (net (code "50") (name "unconnected-(PSoC-P1_6-Pad64)") (class "Default")
      (node (ref "PSoC") (pin "64") (pinfunction "P1_6_64") (pintype "bidirectional"))
    )
    (net (code "51") (name "unconnected-(PSoC-P1_7_VREF-Pad1)") (class "Default")
      (node (ref "PSoC") (pin "1") (pinfunction "P1_7_VREF_1") (pintype "bidirectional"))
    )
    (net (code "52") (name "unconnected-(PSoC-P3_0-Pad18)") (class "Default")
      (node (ref "PSoC") (pin "18") (pinfunction "P3_0_18") (pintype "bidirectional"))
    )
    (net (code "53") (name "unconnected-(PSoC-P3_1-Pad19)") (class "Default")
      (node (ref "PSoC") (pin "19") (pinfunction "P3_1_19") (pintype "bidirectional"))
    )
    (net (code "54") (name "unconnected-(PSoC-P3_2-Pad20)") (class "Default")
      (node (ref "PSoC") (pin "20") (pinfunction "P3_2_20") (pintype "bidirectional"))
    )
    (net (code "55") (name "unconnected-(PSoC-P3_3-Pad21)") (class "Default")
      (node (ref "PSoC") (pin "21") (pinfunction "P3_3_21") (pintype "bidirectional"))
    )
    (net (code "56") (name "unconnected-(PSoC-P3_4-Pad22)") (class "Default")
      (node (ref "PSoC") (pin "22") (pinfunction "P3_4_22") (pintype "bidirectional"))
    )
    (net (code "57") (name "unconnected-(PSoC-P3_5-Pad23)") (class "Default")
      (node (ref "PSoC") (pin "23") (pinfunction "P3_5_23") (pintype "bidirectional"))
    )
    (net (code "58") (name "unconnected-(PSoC-P3_6-Pad24)") (class "Default")
      (node (ref "PSoC") (pin "24") (pinfunction "P3_6_24") (pintype "bidirectional"))
    )
    (net (code "59") (name "unconnected-(PSoC-P3_7-Pad25)") (class "Default")
      (node (ref "PSoC") (pin "25") (pinfunction "P3_7_25") (pintype "bidirectional"))
    )
    (net (code "60") (name "unconnected-(PSoC-P4_0-Pad27)") (class "Default")
      (node (ref "PSoC") (pin "27") (pinfunction "P4_0_27") (pintype "bidirectional"))
    )
    (net (code "61") (name "unconnected-(PSoC-P4_1-Pad28)") (class "Default")
      (node (ref "PSoC") (pin "28") (pinfunction "P4_1_28") (pintype "bidirectional"))
    )
    (net (code "62") (name "unconnected-(PSoC-P4_2-Pad29)") (class "Default")
      (node (ref "PSoC") (pin "29") (pinfunction "P4_2_29") (pintype "bidirectional"))
    )
    (net (code "63") (name "unconnected-(PSoC-P4_3-Pad30)") (class "Default")
      (node (ref "PSoC") (pin "30") (pinfunction "P4_3_30") (pintype "bidirectional"))
    )
    (net (code "64") (name "unconnected-(PSoC-P4_4-Pad31)") (class "Default")
      (node (ref "PSoC") (pin "31") (pinfunction "P4_4_31") (pintype "bidirectional"))
    )
    (net (code "65") (name "unconnected-(PSoC-P4_5-Pad32)") (class "Default")
      (node (ref "PSoC") (pin "32") (pinfunction "P4_5_32") (pintype "bidirectional"))
    )
    (net (code "66") (name "unconnected-(PSoC-P4_6-Pad33)") (class "Default")
      (node (ref "PSoC") (pin "33") (pinfunction "P4_6_33") (pintype "bidirectional"))
    )
    (net (code "67") (name "unconnected-(PSoC-P5_0-Pad51)") (class "Default")
      (node (ref "PSoC") (pin "51") (pinfunction "P5_0_51") (pintype "bidirectional"))
    )
    (net (code "68") (name "unconnected-(PSoC-P5_1-Pad52)") (class "Default")
      (node (ref "PSoC") (pin "52") (pinfunction "P5_1_52") (pintype "bidirectional"))
    )
    (net (code "69") (name "unconnected-(PSoC-P5_2-Pad53)") (class "Default")
      (node (ref "PSoC") (pin "53") (pinfunction "P5_2_53") (pintype "bidirectional"))
    )
    (net (code "70") (name "unconnected-(PSoC-P5_3-Pad54)") (class "Default")
      (node (ref "PSoC") (pin "54") (pinfunction "P5_3_54") (pintype "bidirectional"))
    )
    (net (code "71") (name "unconnected-(PSoC-P5_5-Pad55)") (class "Default")
      (node (ref "PSoC") (pin "55") (pinfunction "P5_5_55") (pintype "bidirectional"))
    )
    (net (code "72") (name "unconnected-(PSoC-P6_0-Pad12)") (class "Default")
      (node (ref "PSoC") (pin "12") (pinfunction "P6_0_12") (pintype "bidirectional"))
    )
    (net (code "73") (name "unconnected-(PSoC-P6_1-Pad13)") (class "Default")
      (node (ref "PSoC") (pin "13") (pinfunction "P6_1_13") (pintype "bidirectional"))
    )
    (net (code "74") (name "unconnected-(PSoC-P6_2-Pad14)") (class "Default")
      (node (ref "PSoC") (pin "14") (pinfunction "P6_2_14") (pintype "bidirectional"))
    )
    (net (code "75") (name "unconnected-(PSoC-P6_4_P12_0-Pad15)") (class "Default")
      (node (ref "PSoC") (pin "15") (pinfunction "P6_4_P12_0_15") (pintype "bidirectional"))
    )
    (net (code "76") (name "unconnected-(PSoC-P6_5_P12_1-Pad16)") (class "Default")
      (node (ref "PSoC") (pin "16") (pinfunction "P6_5_P12_1_16") (pintype "bidirectional"))
    )
    (net (code "77") (name "unconnected-(PSoC-P7_0-Pad37)") (class "Default")
      (node (ref "PSoC") (pin "37") (pinfunction "P7_0_37") (pintype "bidirectional"))
    )
    (net (code "78") (name "unconnected-(PSoC-P7_1-Pad38)") (class "Default")
      (node (ref "PSoC") (pin "38") (pinfunction "P7_1_38") (pintype "bidirectional"))
    )
    (net (code "79") (name "unconnected-(PSoC-VBUS_P13_2-Pad36)") (class "Default")
      (node (ref "PSoC") (pin "36") (pinfunction "VBUS_P13_2_36") (pintype "bidirectional"))
    )
    (net (code "80") (name "unconnected-(PSoC-VCCD-Pad48)") (class "Default")
      (node (ref "PSoC") (pin "48") (pinfunction "VCCD_48") (pintype "power_in"))
    )
    (net (code "81") (name "unconnected-(Program Header-Pad6)") (class "Default")
      (node (ref "Program Header") (pin "6") (pinfunction "6_6") (pintype "passive"))
    )
    (net (code "82") (name "unconnected-(Program Header-Pad7)") (class "Default")
      (node (ref "Program Header") (pin "7") (pinfunction "7_7") (pintype "passive"))
    )
    (net (code "83") (name "unconnected-(Program Header-Pad8)") (class "Default")
      (node (ref "Program Header") (pin "8") (pinfunction "8_8") (pintype "passive"))
    )
  )
)
